# pcb.net
KiCad netlist of a schematic drawn in EasyEDA
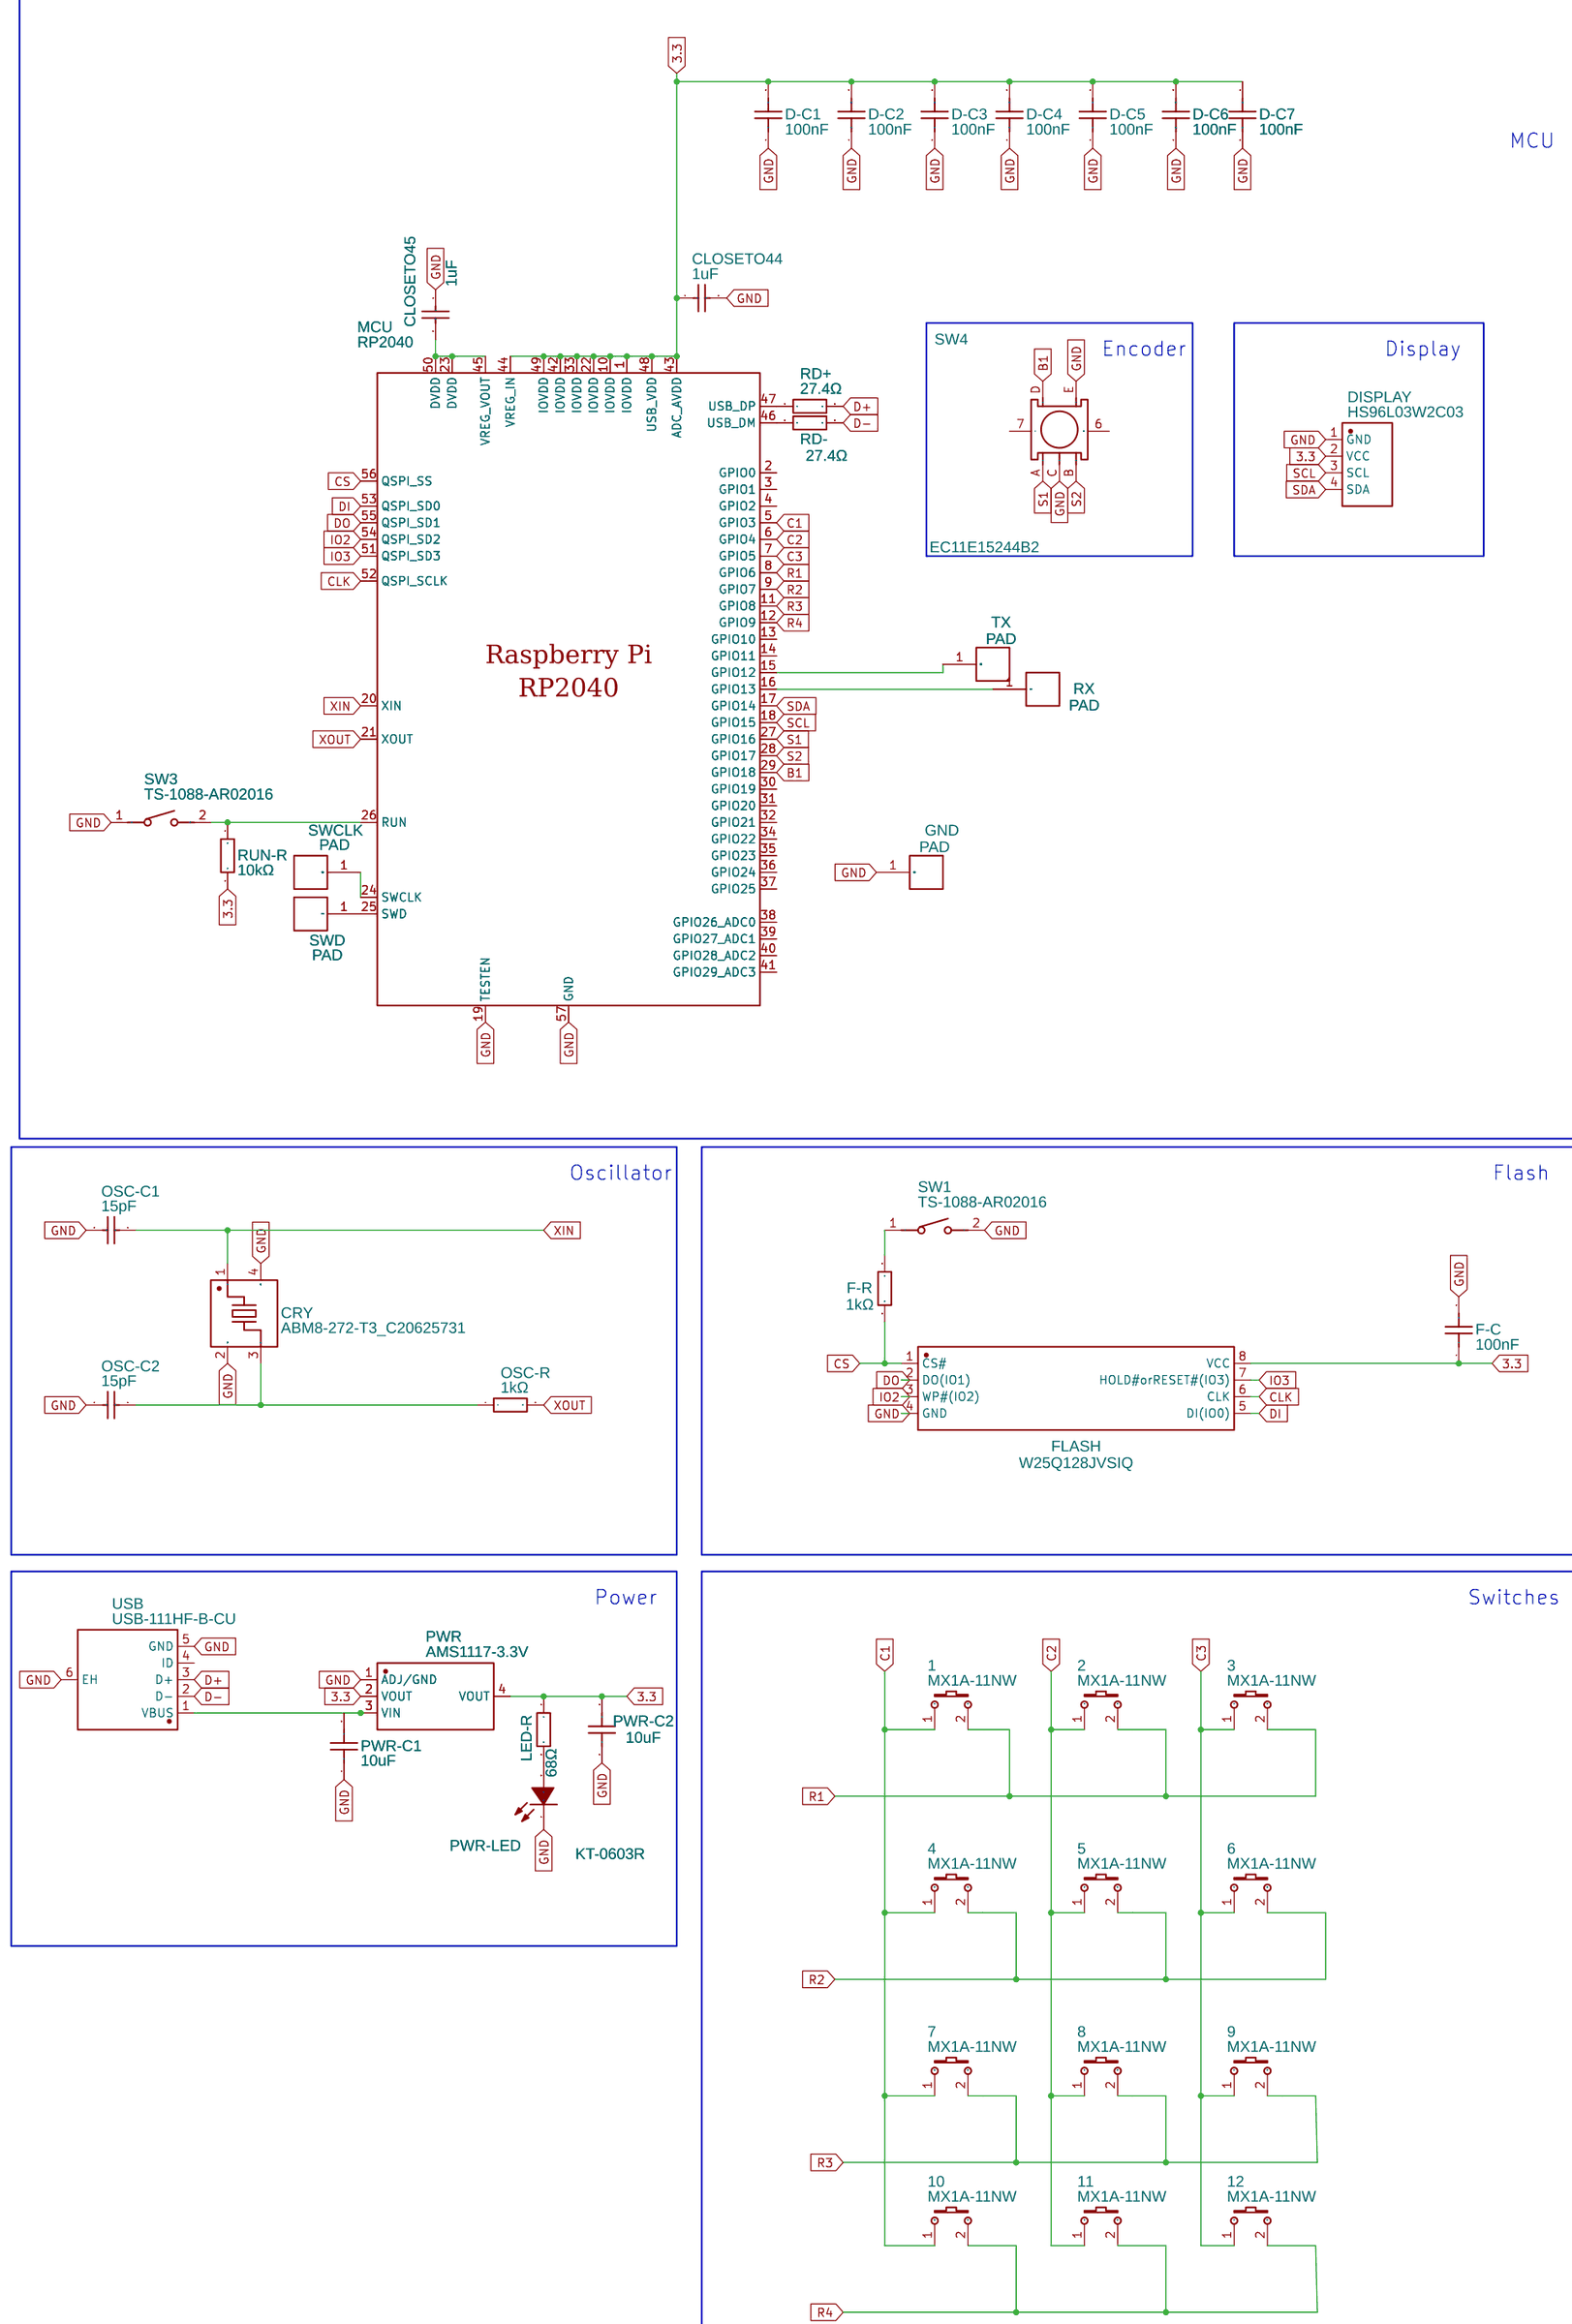
[diagram p0: schematic sheet]

(export (version "E")
  (design (tool "Eeschema 10.0.6"))
  (components
    (comp (ref "1")
      (value "MX1A-11NW")
      (fields (field (name "Manufacturer") "CHERRY"))
      (libsource (lib "") (part "MX1A-11NW"))
    )
    (comp (ref "2")
      (value "MX1A-11NW")
      (fields (field (name "Manufacturer") "CHERRY"))
      (libsource (lib "") (part "MX1A-11NW"))
    )
    (comp (ref "3")
      (value "MX1A-11NW")
      (fields (field (name "Manufacturer") "CHERRY"))
      (libsource (lib "") (part "MX1A-11NW"))
    )
    (comp (ref "4")
      (value "MX1A-11NW")
      (fields (field (name "Manufacturer") "CHERRY"))
      (libsource (lib "") (part "MX1A-11NW"))
    )
    (comp (ref "5")
      (value "MX1A-11NW")
      (fields (field (name "Manufacturer") "CHERRY"))
      (libsource (lib "") (part "MX1A-11NW"))
    )
    (comp (ref "6")
      (value "MX1A-11NW")
      (fields (field (name "Manufacturer") "CHERRY"))
      (libsource (lib "") (part "MX1A-11NW"))
    )
    (comp (ref "7")
      (value "MX1A-11NW")
      (fields (field (name "Manufacturer") "CHERRY"))
      (libsource (lib "") (part "MX1A-11NW"))
    )
    (comp (ref "8")
      (value "MX1A-11NW")
      (fields (field (name "Manufacturer") "CHERRY"))
      (libsource (lib "") (part "MX1A-11NW"))
    )
    (comp (ref "9")
      (value "MX1A-11NW")
      (fields (field (name "Manufacturer") "CHERRY"))
      (libsource (lib "") (part "MX1A-11NW"))
    )
    (comp (ref "10")
      (value "MX1A-11NW")
      (fields (field (name "Manufacturer") "CHERRY"))
      (libsource (lib "") (part "MX1A-11NW"))
    )
    (comp (ref "11")
      (value "MX1A-11NW")
      (fields (field (name "Manufacturer") "CHERRY"))
      (libsource (lib "") (part "MX1A-11NW"))
    )
    (comp (ref "12")
      (value "MX1A-11NW")
      (fields (field (name "Manufacturer") "CHERRY"))
      (libsource (lib "") (part "MX1A-11NW"))
    )
    (comp (ref "CLOSETO44")
      (value "1uF")
      (fields
        (field (name "Manufacturer Part") "GRM155R61E105KA12D")
        (field (name "Manufacturer") "muRata(村田)")
      )
      (libsource (lib "") (part "GRM155R61E105KA12D_1"))
    )
    (comp (ref "CLOSETO45")
      (value "1uF")
      (fields
        (field (name "Manufacturer Part") "GRM155R61E105KA12D")
        (field (name "Manufacturer") "muRata(村田)")
      )
      (libsource (lib "") (part "GRM155R61E105KA12D"))
    )
    (comp (ref "CRY")
      (value "ABM8-272-T3_C20625731")
      (fields (field (name "Manufacturer Part") "ABM8-272-T3") (field (name "Manufacturer") "ABRACON"))
      (libsource (lib "") (part "ABM8-272-T3_C20625731"))
    )
    (comp (ref "D-C1")
      (value "100nF")
      (fields
        (field (name "Manufacturer Part") "CC0603KRX7R9BB104")
        (field (name "Manufacturer") "YAGEO(国巨)")
      )
      (libsource (lib "") (part "CC0603KRX7R9BB104"))
    )
    (comp (ref "D-C2")
      (value "100nF")
      (fields
        (field (name "Manufacturer Part") "CC0603KRX7R9BB104")
        (field (name "Manufacturer") "YAGEO(国巨)")
      )
      (libsource (lib "") (part "CC0603KRX7R9BB104"))
    )
    (comp (ref "D-C3")
      (value "100nF")
      (fields
        (field (name "Manufacturer Part") "CC0603KRX7R9BB104")
        (field (name "Manufacturer") "YAGEO(国巨)")
      )
      (libsource (lib "") (part "CC0603KRX7R9BB104"))
    )
    (comp (ref "D-C4")
      (value "100nF")
      (fields
        (field (name "Manufacturer Part") "CC0603KRX7R9BB104")
        (field (name "Manufacturer") "YAGEO(国巨)")
      )
      (libsource (lib "") (part "CC0603KRX7R9BB104"))
    )
    (comp (ref "D-C5")
      (value "100nF")
      (fields
        (field (name "Manufacturer Part") "CC0603KRX7R9BB104")
        (field (name "Manufacturer") "YAGEO(国巨)")
      )
      (libsource (lib "") (part "CC0603KRX7R9BB104"))
    )
    (comp (ref "D-C6")
      (value "100nF")
      (fields
        (field (name "Manufacturer Part") "CC0603KRX7R9BB104")
        (field (name "Manufacturer") "YAGEO(国巨)")
      )
      (libsource (lib "") (part "CC0603KRX7R9BB104"))
    )
    (comp (ref "D-C7")
      (value "100nF")
      (fields
        (field (name "Manufacturer Part") "CC0603KRX7R9BB104")
        (field (name "Manufacturer") "YAGEO(国巨)")
      )
      (libsource (lib "") (part "CC0603KRX7R9BB104"))
    )
    (comp (ref "DISPLAY")
      (value "HS96L03W2C03")
      (fields (field (name "Manufacturer") "HS(汉昇)"))
      (libsource (lib "") (part "HS96L03W2C03"))
    )
    (comp (ref "F-C")
      (value "100nF")
      (fields
        (field (name "Manufacturer Part") "CC0603KRX7R9BB104")
        (field (name "Manufacturer") "YAGEO(国巨)")
      )
      (libsource (lib "") (part "CC0603KRX7R9BB104_1"))
    )
    (comp (ref "F-R")
      (value "1kΩ")
      (fields
        (field (name "Manufacturer Part") "0805W8F1001T5E")
        (field (name "Manufacturer") "UNI-ROYAL(厚声)")
      )
      (libsource (lib "") (part "0805W8F1001T5E"))
    )
    (comp (ref "FLASH")
      (value "W25Q128JVSIQ")
      (fields (field (name "Manufacturer") "WINBOND(华邦)"))
      (libsource (lib "") (part "W25Q128JVSIQ"))
    )
    (comp (ref "GND") (value "PAD") (libsource (lib "") (part "PAD_3")))
    (comp (ref "LED-R")
      (value "68Ω")
      (fields
        (field (name "Manufacturer Part") "1206W4F680JT5E")
        (field (name "Manufacturer") "UNI-ROYAL(厚声)")
      )
      (libsource (lib "") (part "1206W4F680JT5E"))
    )
    (comp (ref "MCU")
      (value "RP2040")
      (fields (field (name "Manufacturer") "Raspberry Pi(树莓派)"))
      (libsource (lib "") (part "RP2040"))
    )
    (comp (ref "OSC-C1")
      (value "15pF")
      (fields (field (name "Manufacturer Part") "0805CG150J500NT") (field (name "Manufacturer") "FH(风华)"))
      (libsource (lib "") (part "0805CG150J500NT"))
    )
    (comp (ref "OSC-C2")
      (value "15pF")
      (fields (field (name "Manufacturer Part") "0805CG150J500NT") (field (name "Manufacturer") "FH(风华)"))
      (libsource (lib "") (part "0805CG150J500NT"))
    )
    (comp (ref "OSC-R")
      (value "1kΩ")
      (fields
        (field (name "Manufacturer Part") "0805W8F1001T5E")
        (field (name "Manufacturer") "UNI-ROYAL(厚声)")
      )
      (libsource (lib "") (part "0805W8F1001T5E_1"))
    )
    (comp (ref "PWR")
      (value "AMS1117-3.3V")
      (fields (field (name "Manufacturer") "WPMtek(维攀)"))
      (libsource (lib "") (part "AMS1117-3.3V"))
    )
    (comp (ref "PWR-C1")
      (value "10uF")
      (fields
        (field (name "Manufacturer Part") "CL21A106KAYNNNE")
        (field (name "Manufacturer") "SAMSUNG(三星)")
      )
      (libsource (lib "") (part "CL21A106KAYNNNE"))
    )
    (comp (ref "PWR-C2")
      (value "10uF")
      (fields
        (field (name "Manufacturer Part") "CL21A106KAYNNNE")
        (field (name "Manufacturer") "SAMSUNG(三星)")
      )
      (libsource (lib "") (part "CL21A106KAYNNNE"))
    )
    (comp (ref "PWR-LED")
      (value "KT-0603R")
      (fields (field (name "Manufacturer") "KENTO"))
      (libsource (lib "") (part "KT-0603R"))
    )
    (comp (ref "RD+")
      (value "27.4Ω")
      (fields (field (name "Manufacturer Part") "RS-03K27R4FT") (field (name "Manufacturer") "FH(风华)"))
      (libsource (lib "") (part "RS-03K27R4FT_1"))
    )
    (comp (ref "RD-")
      (value "27.4Ω")
      (fields (field (name "Manufacturer Part") "RS-03K27R4FT") (field (name "Manufacturer") "FH(风华)"))
      (libsource (lib "") (part "RS-03K27R4FT"))
    )
    (comp (ref "RUN-R")
      (value "10kΩ")
      (fields
        (field (name "Manufacturer Part") "0805W8F1002T5E")
        (field (name "Manufacturer") "UNI-ROYAL(厚声)")
      )
      (libsource (lib "") (part "0805W8F1002T5E"))
    )
    (comp (ref "RX") (value "PAD") (libsource (lib "") (part "PAD_1")))
    (comp (ref "SW1")
      (value "TS-1088-AR02016")
      (fields (field (name "Manufacturer") "XUNPU(讯普)"))
      (libsource (lib "") (part "TS-1088-AR02016"))
    )
    (comp (ref "SW3")
      (value "TS-1088-AR02016")
      (fields (field (name "Manufacturer") "XUNPU(讯普)"))
      (libsource (lib "") (part "TS-1088-AR02016"))
    )
    (comp (ref "SW4")
      (value "EC11E15244B2")
      (fields (field (name "Manufacturer") "ALPSALPINE(阿尔卑斯阿尔派)"))
      (libsource (lib "") (part "EC11E15244B2"))
    )
    (comp (ref "SWCLK") (value "PAD") (libsource (lib "") (part "PAD_4")))
    (comp (ref "SWD") (value "PAD") (libsource (lib "") (part "PAD")))
    (comp (ref "TX") (value "PAD") (libsource (lib "") (part "PAD_2")))
    (comp (ref "USB")
      (value "USB-111HF-B-CU")
      (fields (field (name "Manufacturer") "HOOYA(皓宇电子)"))
      (libsource (lib "") (part "USB-111HF-B-CU"))
    )
  )
  (nets
    (net (code "1") (name "3.3") (class "Default")
      (node (ref "CLOSETO44") (pin "1") (pinfunction "1_1") (pintype "input"))
      (node (ref "D-C1") (pin "2") (pinfunction "2_2") (pintype "unspecified"))
      (node (ref "D-C2") (pin "2") (pinfunction "2_2") (pintype "unspecified"))
      (node (ref "D-C3") (pin "2") (pinfunction "2_2") (pintype "unspecified"))
      (node (ref "D-C4") (pin "2") (pinfunction "2_2") (pintype "unspecified"))
      (node (ref "D-C5") (pin "2") (pinfunction "2_2") (pintype "unspecified"))
      (node (ref "D-C6") (pin "2") (pinfunction "2_2") (pintype "unspecified"))
      (node (ref "D-C7") (pin "2") (pinfunction "2_2") (pintype "unspecified"))
      (node (ref "DISPLAY") (pin "2") (pinfunction "VCC_2") (pintype "unspecified"))
      (node (ref "F-C") (pin "1") (pinfunction "1_1") (pintype "unspecified"))
      (node (ref "FLASH") (pin "8") (pinfunction "VCC_8") (pintype "unspecified"))
      (node (ref "LED-R") (pin "1") (pinfunction "1_1") (pintype "input"))
      (node (ref "MCU") (pin "1") (pinfunction "IOVDD_1") (pintype "bidirectional"))
      (node (ref "MCU") (pin "10") (pinfunction "IOVDD_10") (pintype "bidirectional"))
      (node (ref "MCU") (pin "22") (pinfunction "IOVDD_22") (pintype "bidirectional"))
      (node (ref "MCU") (pin "33") (pinfunction "IOVDD_33") (pintype "bidirectional"))
      (node (ref "MCU") (pin "42") (pinfunction "IOVDD_42") (pintype "bidirectional"))
      (node (ref "MCU") (pin "43") (pinfunction "ADC_AVDD_43") (pintype "bidirectional"))
      (node (ref "MCU") (pin "44") (pinfunction "VREG_IN_44") (pintype "bidirectional"))
      (node (ref "MCU") (pin "48") (pinfunction "USB_VDD_48") (pintype "bidirectional"))
      (node (ref "MCU") (pin "49") (pinfunction "IOVDD_49") (pintype "bidirectional"))
      (node (ref "PWR") (pin "2") (pinfunction "VOUT_2") (pintype "unspecified"))
      (node (ref "PWR") (pin "4") (pinfunction "VOUT_4") (pintype "unspecified"))
      (node (ref "PWR-C2") (pin "2") (pinfunction "2_2") (pintype "unspecified"))
      (node (ref "RUN-R") (pin "2") (pinfunction "2_2") (pintype "input"))
    )
    (net (code "2") (name "B1") (class "Default")
      (node (ref "MCU") (pin "29") (pinfunction "GPIO18_29") (pintype "bidirectional"))
      (node (ref "SW4") (pin "D") (pinfunction "D_D") (pintype "unspecified"))
    )
    (net (code "3") (name "C1") (class "Default")
      (node (ref "1") (pin "1") (pinfunction "1_1") (pintype "unspecified"))
      (node (ref "10") (pin "1") (pinfunction "1_1") (pintype "unspecified"))
      (node (ref "4") (pin "1") (pinfunction "1_1") (pintype "unspecified"))
      (node (ref "7") (pin "1") (pinfunction "1_1") (pintype "unspecified"))
      (node (ref "MCU") (pin "5") (pinfunction "GPIO3_5") (pintype "bidirectional"))
    )
    (net (code "4") (name "C2") (class "Default")
      (node (ref "11") (pin "1") (pinfunction "1_1") (pintype "unspecified"))
      (node (ref "2") (pin "1") (pinfunction "1_1") (pintype "unspecified"))
      (node (ref "5") (pin "1") (pinfunction "1_1") (pintype "unspecified"))
      (node (ref "8") (pin "1") (pinfunction "1_1") (pintype "unspecified"))
      (node (ref "MCU") (pin "6") (pinfunction "GPIO4_6") (pintype "bidirectional"))
    )
    (net (code "5") (name "C3") (class "Default")
      (node (ref "12") (pin "1") (pinfunction "1_1") (pintype "unspecified"))
      (node (ref "3") (pin "1") (pinfunction "1_1") (pintype "unspecified"))
      (node (ref "6") (pin "1") (pinfunction "1_1") (pintype "unspecified"))
      (node (ref "9") (pin "1") (pinfunction "1_1") (pintype "unspecified"))
      (node (ref "MCU") (pin "7") (pinfunction "GPIO5_7") (pintype "bidirectional"))
    )
    (net (code "6") (name "CLK") (class "Default")
      (node (ref "FLASH") (pin "6") (pinfunction "CLK_6") (pintype "unspecified"))
      (node (ref "MCU") (pin "52") (pinfunction "QSPI_SCLK_52") (pintype "output"))
    )
    (net (code "7") (name "CS") (class "Default")
      (node (ref "F-R") (pin "2") (pinfunction "2_2") (pintype "input"))
      (node (ref "FLASH") (pin "1") (pinfunction "CS#_1") (pintype "unspecified"))
      (node (ref "MCU") (pin "56") (pinfunction "QSPI_SS_56") (pintype "bidirectional"))
    )
    (net (code "8") (name "D+") (class "Default")
      (node (ref "RD+") (pin "2") (pinfunction "2_2") (pintype "unspecified"))
      (node (ref "USB") (pin "3") (pinfunction "D+_3") (pintype "unspecified"))
    )
    (net (code "9") (name "D-") (class "Default")
      (node (ref "RD-") (pin "2") (pinfunction "2_2") (pintype "unspecified"))
      (node (ref "USB") (pin "2") (pinfunction "D-_2") (pintype "unspecified"))
    )
    (net (code "10") (name "DI") (class "Default")
      (node (ref "FLASH") (pin "5") (pinfunction "DI(IO0)_5") (pintype "unspecified"))
      (node (ref "MCU") (pin "53") (pinfunction "QSPI_SD0_53") (pintype "bidirectional"))
    )
    (net (code "11") (name "DO") (class "Default")
      (node (ref "FLASH") (pin "2") (pinfunction "DO(IO1)_2") (pintype "unspecified"))
      (node (ref "MCU") (pin "55") (pinfunction "QSPI_SD1_55") (pintype "bidirectional"))
    )
    (net (code "12") (name "GND") (class "Default")
      (node (ref "CLOSETO44") (pin "2") (pinfunction "2_2") (pintype "input"))
      (node (ref "CLOSETO45") (pin "1") (pinfunction "1_1") (pintype "input"))
      (node (ref "CRY") (pin "2") (pinfunction "GND_2") (pintype "input"))
      (node (ref "CRY") (pin "4") (pinfunction "GND_4") (pintype "input"))
      (node (ref "D-C1") (pin "1") (pinfunction "1_1") (pintype "unspecified"))
      (node (ref "D-C2") (pin "1") (pinfunction "1_1") (pintype "unspecified"))
      (node (ref "D-C3") (pin "1") (pinfunction "1_1") (pintype "unspecified"))
      (node (ref "D-C4") (pin "1") (pinfunction "1_1") (pintype "unspecified"))
      (node (ref "D-C5") (pin "1") (pinfunction "1_1") (pintype "unspecified"))
      (node (ref "D-C6") (pin "1") (pinfunction "1_1") (pintype "unspecified"))
      (node (ref "D-C7") (pin "1") (pinfunction "1_1") (pintype "unspecified"))
      (node (ref "DISPLAY") (pin "1") (pinfunction "GND_1") (pintype "unspecified"))
      (node (ref "F-C") (pin "2") (pinfunction "2_2") (pintype "unspecified"))
      (node (ref "FLASH") (pin "4") (pinfunction "GND_4") (pintype "unspecified"))
      (node (ref "GND") (pin "1") (pinfunction "PADPAD123_1") (pintype "unspecified"))
      (node (ref "MCU") (pin "19") (pinfunction "TESTEN_19") (pintype "unspecified"))
      (node (ref "MCU") (pin "57") (pinfunction "GND_57") (pintype "bidirectional"))
      (node (ref "OSC-C1") (pin "2") (pinfunction "2_2") (pintype "input"))
      (node (ref "OSC-C2") (pin "2") (pinfunction "2_2") (pintype "input"))
      (node (ref "PWR") (pin "1") (pinfunction "ADJ/GND_1") (pintype "unspecified"))
      (node (ref "PWR-C1") (pin "1") (pinfunction "1_1") (pintype "unspecified"))
      (node (ref "PWR-C2") (pin "1") (pinfunction "1_1") (pintype "unspecified"))
      (node (ref "PWR-LED") (pin "1") (pinfunction "K_1") (pintype "unspecified"))
      (node (ref "SW1") (pin "2") (pinfunction "2_2") (pintype "unspecified"))
      (node (ref "SW3") (pin "1") (pinfunction "1_1") (pintype "unspecified"))
      (node (ref "SW4") (pin "C") (pinfunction "C_C") (pintype "unspecified"))
      (node (ref "SW4") (pin "E") (pinfunction "E_E") (pintype "unspecified"))
      (node (ref "USB") (pin "5") (pinfunction "GND_5") (pintype "unspecified"))
      (node (ref "USB") (pin "6") (pinfunction "EH_6") (pintype "unspecified"))
    )
    (net (code "13") (name "IO2") (class "Default")
      (node (ref "FLASH") (pin "3") (pinfunction "WP#(IO2)_3") (pintype "unspecified"))
      (node (ref "MCU") (pin "54") (pinfunction "QSPI_SD2_54") (pintype "bidirectional"))
    )
    (net (code "14") (name "IO3") (class "Default")
      (node (ref "FLASH") (pin "7") (pinfunction "HOLD#orRESET#(IO3)_7") (pintype "unspecified"))
      (node (ref "MCU") (pin "51") (pinfunction "QSPI_SD3_51") (pintype "bidirectional"))
    )
    (net (code "15") (name "Net-(CRY-Pad3)") (class "Default")
      (node (ref "CRY") (pin "3") (pinfunction "3_3") (pintype "input"))
      (node (ref "OSC-C2") (pin "1") (pinfunction "1_1") (pintype "input"))
      (node (ref "OSC-R") (pin "1") (pinfunction "1_1") (pintype "input"))
    )
    (net (code "16") (name "Net-(F-R-Pad1)") (class "Default")
      (node (ref "F-R") (pin "1") (pinfunction "1_1") (pintype "input"))
      (node (ref "SW1") (pin "1") (pinfunction "1_1") (pintype "unspecified"))
    )
    (net (code "17") (name "Net-(MCU-GPIO12)") (class "Default")
      (node (ref "MCU") (pin "15") (pinfunction "GPIO12_15") (pintype "bidirectional"))
      (node (ref "TX") (pin "1") (pinfunction "PADPAD123_1") (pintype "unspecified"))
    )
    (net (code "18") (name "Net-(MCU-GPIO13)") (class "Default")
      (node (ref "MCU") (pin "16") (pinfunction "GPIO13_16") (pintype "bidirectional"))
      (node (ref "RX") (pin "1") (pinfunction "PADPAD123_1") (pintype "unspecified"))
    )
    (net (code "19") (name "Net-(MCU-RUN)") (class "Default")
      (node (ref "MCU") (pin "26") (pinfunction "RUN_26") (pintype "input"))
      (node (ref "RUN-R") (pin "1") (pinfunction "1_1") (pintype "input"))
      (node (ref "SW3") (pin "2") (pinfunction "2_2") (pintype "unspecified"))
    )
    (net (code "20") (name "Net-(MCU-SWCLK)") (class "Default")
      (node (ref "MCU") (pin "24") (pinfunction "SWCLK_24") (pintype "output"))
      (node (ref "SWCLK") (pin "1") (pinfunction "PADPAD123_1") (pintype "unspecified"))
    )
    (net (code "21") (name "Net-(MCU-SWD)") (class "Default")
      (node (ref "MCU") (pin "25") (pinfunction "SWD_25") (pintype "bidirectional"))
      (node (ref "SWD") (pin "1") (pinfunction "PADPAD123_1") (pintype "unspecified"))
    )
    (net (code "22") (name "Net-(MCU-USB_DM)") (class "Default")
      (node (ref "MCU") (pin "46") (pinfunction "USB_DM_46") (pintype "bidirectional"))
      (node (ref "RD-") (pin "1") (pinfunction "1_1") (pintype "unspecified"))
    )
    (net (code "23") (name "Net-(MCU-USB_DP)") (class "Default")
      (node (ref "MCU") (pin "47") (pinfunction "USB_DP_47") (pintype "bidirectional"))
      (node (ref "RD+") (pin "1") (pinfunction "1_1") (pintype "unspecified"))
    )
    (net (code "24") (name "Net-(MCU-VREG_VOUT)") (class "Default")
      (node (ref "CLOSETO45") (pin "2") (pinfunction "2_2") (pintype "input"))
      (node (ref "MCU") (pin "23") (pinfunction "DVDD_23") (pintype "bidirectional"))
      (node (ref "MCU") (pin "45") (pinfunction "VREG_VOUT_45") (pintype "bidirectional"))
      (node (ref "MCU") (pin "50") (pinfunction "DVDD_50") (pintype "bidirectional"))
    )
    (net (code "25") (name "Net-(PWR-LED-A)") (class "Default")
      (node (ref "LED-R") (pin "2") (pinfunction "2_2") (pintype "input"))
      (node (ref "PWR-LED") (pin "2") (pinfunction "A_2") (pintype "unspecified"))
    )
    (net (code "26") (name "Net-(PWR-VIN)") (class "Default")
      (node (ref "PWR") (pin "3") (pinfunction "VIN_3") (pintype "unspecified"))
      (node (ref "PWR-C1") (pin "2") (pinfunction "2_2") (pintype "unspecified"))
      (node (ref "USB") (pin "1") (pinfunction "VBUS_1") (pintype "unspecified"))
    )
    (net (code "27") (name "R1") (class "Default")
      (node (ref "1") (pin "2") (pinfunction "2_2") (pintype "unspecified"))
      (node (ref "2") (pin "2") (pinfunction "2_2") (pintype "unspecified"))
      (node (ref "3") (pin "2") (pinfunction "2_2") (pintype "unspecified"))
      (node (ref "MCU") (pin "8") (pinfunction "GPIO6_8") (pintype "bidirectional"))
    )
    (net (code "28") (name "R2") (class "Default")
      (node (ref "4") (pin "2") (pinfunction "2_2") (pintype "unspecified"))
      (node (ref "5") (pin "2") (pinfunction "2_2") (pintype "unspecified"))
      (node (ref "6") (pin "2") (pinfunction "2_2") (pintype "unspecified"))
      (node (ref "MCU") (pin "9") (pinfunction "GPIO7_9") (pintype "bidirectional"))
    )
    (net (code "29") (name "R3") (class "Default")
      (node (ref "7") (pin "2") (pinfunction "2_2") (pintype "unspecified"))
      (node (ref "8") (pin "2") (pinfunction "2_2") (pintype "unspecified"))
      (node (ref "9") (pin "2") (pinfunction "2_2") (pintype "unspecified"))
      (node (ref "MCU") (pin "11") (pinfunction "GPIO8_11") (pintype "bidirectional"))
    )
    (net (code "30") (name "R4") (class "Default")
      (node (ref "10") (pin "2") (pinfunction "2_2") (pintype "unspecified"))
      (node (ref "11") (pin "2") (pinfunction "2_2") (pintype "unspecified"))
      (node (ref "12") (pin "2") (pinfunction "2_2") (pintype "unspecified"))
      (node (ref "MCU") (pin "12") (pinfunction "GPIO9_12") (pintype "bidirectional"))
    )
    (net (code "31") (name "S1") (class "Default")
      (node (ref "MCU") (pin "27") (pinfunction "GPIO16_27") (pintype "bidirectional"))
      (node (ref "SW4") (pin "A") (pinfunction "A_A") (pintype "unspecified"))
    )
    (net (code "32") (name "S2") (class "Default")
      (node (ref "MCU") (pin "28") (pinfunction "GPIO17_28") (pintype "bidirectional"))
      (node (ref "SW4") (pin "B") (pinfunction "B_B") (pintype "unspecified"))
    )
    (net (code "33") (name "SCL") (class "Default")
      (node (ref "DISPLAY") (pin "3") (pinfunction "SCL_3") (pintype "unspecified"))
      (node (ref "MCU") (pin "18") (pinfunction "GPIO15_18") (pintype "bidirectional"))
    )
    (net (code "34") (name "SDA") (class "Default")
      (node (ref "DISPLAY") (pin "4") (pinfunction "SDA_4") (pintype "unspecified"))
      (node (ref "MCU") (pin "17") (pinfunction "GPIO14_17") (pintype "bidirectional"))
    )
    (net (code "35") (name "XIN") (class "Default")
      (node (ref "CRY") (pin "1") (pinfunction "1_1") (pintype "input"))
      (node (ref "MCU") (pin "20") (pinfunction "XIN_20") (pintype "input"))
      (node (ref "OSC-C1") (pin "1") (pinfunction "1_1") (pintype "input"))
    )
    (net (code "36") (name "XOUT") (class "Default")
      (node (ref "MCU") (pin "21") (pinfunction "XOUT_21") (pintype "unspecified"))
      (node (ref "OSC-R") (pin "2") (pinfunction "2_2") (pintype "input"))
    )
    (net (code "37") (name "unconnected-(MCU-GPIO0-Pad2)") (class "Default")
      (node (ref "MCU") (pin "2") (pinfunction "GPIO0_2") (pintype "bidirectional"))
    )
    (net (code "38") (name "unconnected-(MCU-GPIO1-Pad3)") (class "Default")
      (node (ref "MCU") (pin "3") (pinfunction "GPIO1_3") (pintype "bidirectional"))
    )
    (net (code "39") (name "unconnected-(MCU-GPIO2-Pad4)") (class "Default")
      (node (ref "MCU") (pin "4") (pinfunction "GPIO2_4") (pintype "bidirectional"))
    )
    (net (code "40") (name "unconnected-(MCU-GPIO10-Pad13)") (class "Default")
      (node (ref "MCU") (pin "13") (pinfunction "GPIO10_13") (pintype "bidirectional"))
    )
    (net (code "41") (name "unconnected-(MCU-GPIO11-Pad14)") (class "Default")
      (node (ref "MCU") (pin "14") (pinfunction "GPIO11_14") (pintype "bidirectional"))
    )
    (net (code "42") (name "unconnected-(MCU-GPIO19-Pad30)") (class "Default")
      (node (ref "MCU") (pin "30") (pinfunction "GPIO19_30") (pintype "bidirectional"))
    )
    (net (code "43") (name "unconnected-(MCU-GPIO20-Pad31)") (class "Default")
      (node (ref "MCU") (pin "31") (pinfunction "GPIO20_31") (pintype "bidirectional"))
    )
    (net (code "44") (name "unconnected-(MCU-GPIO21-Pad32)") (class "Default")
      (node (ref "MCU") (pin "32") (pinfunction "GPIO21_32") (pintype "bidirectional"))
    )
    (net (code "45") (name "unconnected-(MCU-GPIO22-Pad34)") (class "Default")
      (node (ref "MCU") (pin "34") (pinfunction "GPIO22_34") (pintype "bidirectional"))
    )
    (net (code "46") (name "unconnected-(MCU-GPIO23-Pad35)") (class "Default")
      (node (ref "MCU") (pin "35") (pinfunction "GPIO23_35") (pintype "bidirectional"))
    )
    (net (code "47") (name "unconnected-(MCU-GPIO24-Pad36)") (class "Default")
      (node (ref "MCU") (pin "36") (pinfunction "GPIO24_36") (pintype "bidirectional"))
    )
    (net (code "48") (name "unconnected-(MCU-GPIO25-Pad37)") (class "Default")
      (node (ref "MCU") (pin "37") (pinfunction "GPIO25_37") (pintype "bidirectional"))
    )
    (net (code "49") (name "unconnected-(MCU-GPIO26_ADC0-Pad38)") (class "Default")
      (node (ref "MCU") (pin "38") (pinfunction "GPIO26_ADC0_38") (pintype "bidirectional"))
    )
    (net (code "50") (name "unconnected-(MCU-GPIO27_ADC1-Pad39)") (class "Default")
      (node (ref "MCU") (pin "39") (pinfunction "GPIO27_ADC1_39") (pintype "bidirectional"))
    )
    (net (code "51") (name "unconnected-(MCU-GPIO28_ADC2-Pad40)") (class "Default")
      (node (ref "MCU") (pin "40") (pinfunction "GPIO28_ADC2_40") (pintype "bidirectional"))
    )
    (net (code "52") (name "unconnected-(MCU-GPIO29_ADC3-Pad41)") (class "Default")
      (node (ref "MCU") (pin "41") (pinfunction "GPIO29_ADC3_41") (pintype "bidirectional"))
    )
    (net (code "53") (name "unconnected-(SW4-Pad6)") (class "Default")
      (node (ref "SW4") (pin "6") (pinfunction "6_6") (pintype "unspecified"))
    )
    (net (code "54") (name "unconnected-(SW4-Pad7)") (class "Default")
      (node (ref "SW4") (pin "7") (pinfunction "7_7") (pintype "unspecified"))
    )
    (net (code "55") (name "unconnected-(USB-ID-Pad4)") (class "Default")
      (node (ref "USB") (pin "4") (pinfunction "ID_4") (pintype "unspecified"))
    )
  )
)
